# Dionysus_FPGA.net
KiCad netlist of a schematic drawn in Altium Designer
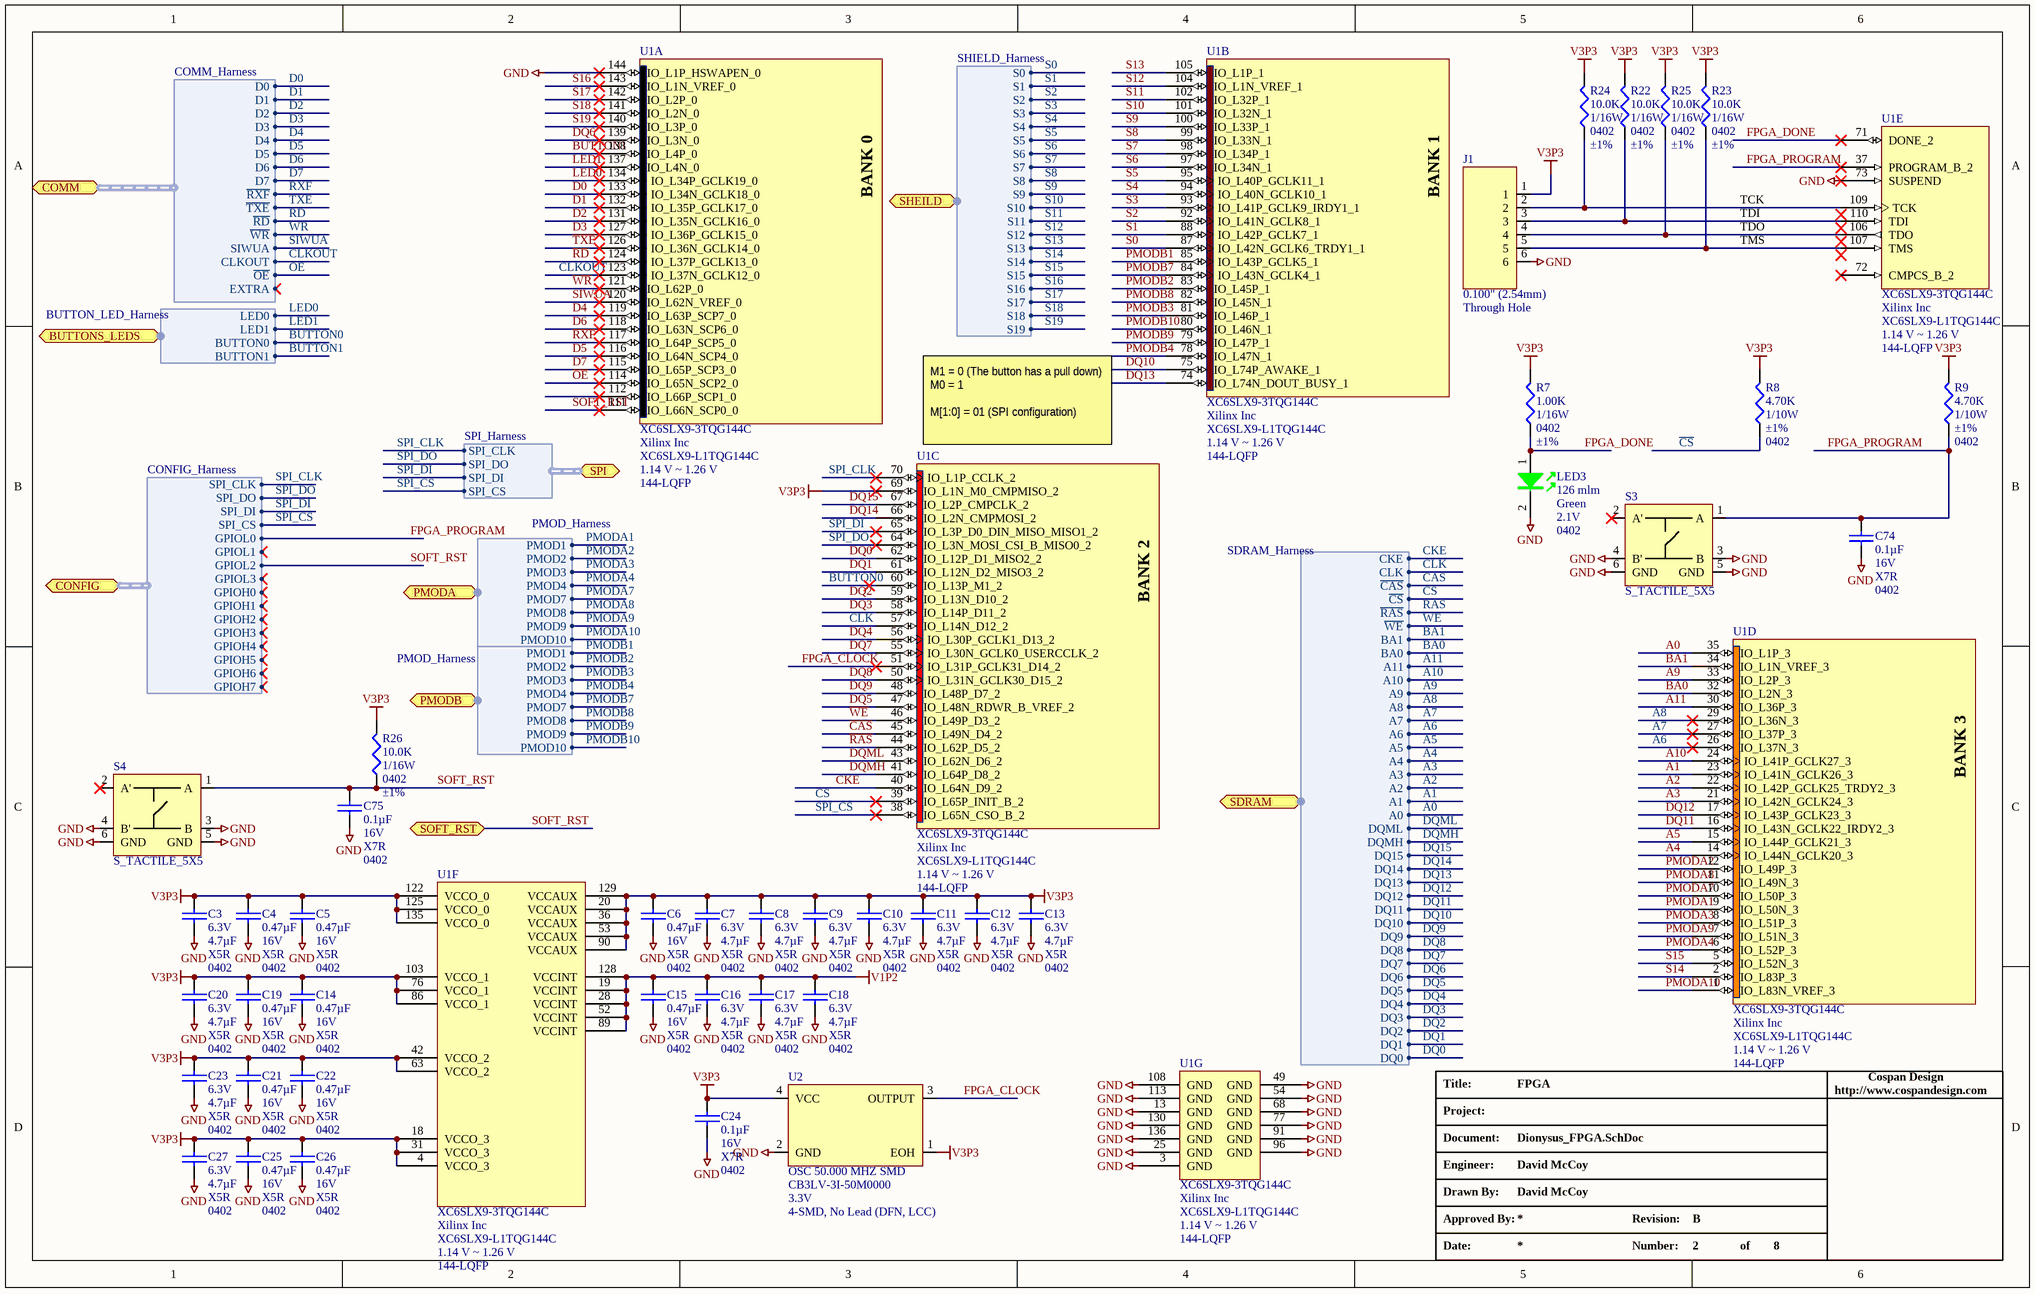
[diagram p0: Dionysus_FPGA.SchDoc]

(export (version "E")
  (design (tool "Eeschema 10.0.6"))
  (components
    (comp (ref "C3")
      (value "4.7uF")
      (footprint "C_ERA-0402")
      (description "CAP CER 4.7UF 6.3V X5R 0402")
      (fields
        (field (name "MANUFACTURER") "Murata Electronics North America")
        (field (name "MANUFACTURER PART NUMBER") "GRM155R60J475ME87D")
        (field (name "VOLTAGE - RATED") "6.3V")
        (field (name "CAPACITANCE") "4.7µF")
        (field (name "TEMPERATURE COEFFICIENT") "X5R")
        (field (name "PACKAGE / CASE") "0402")
      )
      (libsource (lib "Main LibraryX") (part "C_0402_4.7UF"))
    )
    (comp (ref "C4")
      (value "0.47uF")
      (footprint "C_ERA-0402")
      (description "CAP CER .47UF 16V X5R 0402")
      (fields
        (field (name "TOLERANCE") "±10%")
        (field (name "MANUFACTURER") "TDK Corporation")
        (field (name "CAPACITANCE") "0.47µF")
        (field (name "VOLTAGE - RATED") "16V")
        (field (name "TEMPERATURE COEFFICIENT") "X5R")
        (field (name "PACKAGE / CASE") "0402")
      )
      (libsource (lib "Main LibraryX") (part "C_0402_0.47UF"))
    )
    (comp (ref "C5")
      (value "0.47uF")
      (footprint "C_ERA-0402")
      (description "CAP CER .47UF 16V X5R 0402")
      (fields
        (field (name "TOLERANCE") "±10%")
        (field (name "MANUFACTURER") "TDK Corporation")
        (field (name "CAPACITANCE") "0.47µF")
        (field (name "VOLTAGE - RATED") "16V")
        (field (name "TEMPERATURE COEFFICIENT") "X5R")
        (field (name "PACKAGE / CASE") "0402")
      )
      (libsource (lib "Main LibraryX") (part "C_0402_0.47UF"))
    )
    (comp (ref "C6")
      (value "0.47uF")
      (footprint "C_ERA-0402")
      (description "CAP CER .47UF 16V X5R 0402")
      (fields
        (field (name "TOLERANCE") "±10%")
        (field (name "MANUFACTURER") "TDK Corporation")
        (field (name "CAPACITANCE") "0.47µF")
        (field (name "VOLTAGE - RATED") "16V")
        (field (name "TEMPERATURE COEFFICIENT") "X5R")
        (field (name "PACKAGE / CASE") "0402")
      )
      (libsource (lib "Main LibraryX") (part "C_0402_0.47UF"))
    )
    (comp (ref "C7")
      (value "4.7uF")
      (footprint "C_ERA-0402")
      (description "CAP CER 4.7UF 6.3V X5R 0402")
      (fields
        (field (name "MANUFACTURER") "Murata Electronics North America")
        (field (name "MANUFACTURER PART NUMBER") "GRM155R60J475ME87D")
        (field (name "VOLTAGE - RATED") "6.3V")
        (field (name "CAPACITANCE") "4.7µF")
        (field (name "TEMPERATURE COEFFICIENT") "X5R")
        (field (name "PACKAGE / CASE") "0402")
      )
      (libsource (lib "Main LibraryX") (part "C_0402_4.7UF"))
    )
    (comp (ref "C8")
      (value "4.7uF")
      (footprint "C_ERA-0402")
      (description "CAP CER 4.7UF 6.3V X5R 0402")
      (fields
        (field (name "MANUFACTURER") "Murata Electronics North America")
        (field (name "MANUFACTURER PART NUMBER") "GRM155R60J475ME87D")
        (field (name "VOLTAGE - RATED") "6.3V")
        (field (name "CAPACITANCE") "4.7µF")
        (field (name "TEMPERATURE COEFFICIENT") "X5R")
        (field (name "PACKAGE / CASE") "0402")
      )
      (libsource (lib "Main LibraryX") (part "C_0402_4.7UF"))
    )
    (comp (ref "C9")
      (value "4.7uF")
      (footprint "C_ERA-0402")
      (description "CAP CER 4.7UF 6.3V X5R 0402")
      (fields
        (field (name "MANUFACTURER") "Murata Electronics North America")
        (field (name "MANUFACTURER PART NUMBER") "GRM155R60J475ME87D")
        (field (name "VOLTAGE - RATED") "6.3V")
        (field (name "CAPACITANCE") "4.7µF")
        (field (name "TEMPERATURE COEFFICIENT") "X5R")
        (field (name "PACKAGE / CASE") "0402")
      )
      (libsource (lib "Main LibraryX") (part "C_0402_4.7UF"))
    )
    (comp (ref "C10")
      (value "4.7uF")
      (footprint "C_ERA-0402")
      (description "CAP CER 4.7UF 6.3V X5R 0402")
      (fields
        (field (name "MANUFACTURER") "Murata Electronics North America")
        (field (name "MANUFACTURER PART NUMBER") "GRM155R60J475ME87D")
        (field (name "VOLTAGE - RATED") "6.3V")
        (field (name "CAPACITANCE") "4.7µF")
        (field (name "TEMPERATURE COEFFICIENT") "X5R")
        (field (name "PACKAGE / CASE") "0402")
      )
      (libsource (lib "Main LibraryX") (part "C_0402_4.7UF"))
    )
    (comp (ref "C11")
      (value "4.7uF")
      (footprint "C_ERA-0402")
      (description "CAP CER 4.7UF 6.3V X5R 0402")
      (fields
        (field (name "MANUFACTURER") "Murata Electronics North America")
        (field (name "MANUFACTURER PART NUMBER") "GRM155R60J475ME87D")
        (field (name "VOLTAGE - RATED") "6.3V")
        (field (name "CAPACITANCE") "4.7µF")
        (field (name "TEMPERATURE COEFFICIENT") "X5R")
        (field (name "PACKAGE / CASE") "0402")
      )
      (libsource (lib "Main LibraryX") (part "C_0402_4.7UF"))
    )
    (comp (ref "C12")
      (value "4.7uF")
      (footprint "C_ERA-0402")
      (description "CAP CER 4.7UF 6.3V X5R 0402")
      (fields
        (field (name "MANUFACTURER") "Murata Electronics North America")
        (field (name "MANUFACTURER PART NUMBER") "GRM155R60J475ME87D")
        (field (name "VOLTAGE - RATED") "6.3V")
        (field (name "CAPACITANCE") "4.7µF")
        (field (name "TEMPERATURE COEFFICIENT") "X5R")
        (field (name "PACKAGE / CASE") "0402")
      )
      (libsource (lib "Main LibraryX") (part "C_0402_4.7UF"))
    )
    (comp (ref "C13")
      (value "4.7uF")
      (footprint "C_ERA-0402")
      (description "CAP CER 4.7UF 6.3V X5R 0402")
      (fields
        (field (name "MANUFACTURER") "Murata Electronics North America")
        (field (name "MANUFACTURER PART NUMBER") "GRM155R60J475ME87D")
        (field (name "VOLTAGE - RATED") "6.3V")
        (field (name "CAPACITANCE") "4.7µF")
        (field (name "TEMPERATURE COEFFICIENT") "X5R")
        (field (name "PACKAGE / CASE") "0402")
      )
      (libsource (lib "Main LibraryX") (part "C_0402_4.7UF"))
    )
    (comp (ref "C14")
      (value "0.47uF")
      (footprint "C_ERA-0402")
      (description "CAP CER .47UF 16V X5R 0402")
      (fields
        (field (name "TOLERANCE") "±10%")
        (field (name "MANUFACTURER") "TDK Corporation")
        (field (name "CAPACITANCE") "0.47µF")
        (field (name "VOLTAGE - RATED") "16V")
        (field (name "TEMPERATURE COEFFICIENT") "X5R")
        (field (name "PACKAGE / CASE") "0402")
      )
      (libsource (lib "Main LibraryX") (part "C_0402_0.47UF"))
    )
    (comp (ref "C15")
      (value "0.47uF")
      (footprint "C_ERA-0402")
      (description "CAP CER .47UF 16V X5R 0402")
      (fields
        (field (name "TOLERANCE") "±10%")
        (field (name "MANUFACTURER") "TDK Corporation")
        (field (name "CAPACITANCE") "0.47µF")
        (field (name "VOLTAGE - RATED") "16V")
        (field (name "TEMPERATURE COEFFICIENT") "X5R")
        (field (name "PACKAGE / CASE") "0402")
      )
      (libsource (lib "Main LibraryX") (part "C_0402_0.47UF"))
    )
    (comp (ref "C16")
      (value "4.7uF")
      (footprint "C_ERA-0402")
      (description "CAP CER 4.7UF 6.3V X5R 0402")
      (fields
        (field (name "MANUFACTURER") "Murata Electronics North America")
        (field (name "MANUFACTURER PART NUMBER") "GRM155R60J475ME87D")
        (field (name "VOLTAGE - RATED") "6.3V")
        (field (name "CAPACITANCE") "4.7µF")
        (field (name "TEMPERATURE COEFFICIENT") "X5R")
        (field (name "PACKAGE / CASE") "0402")
      )
      (libsource (lib "Main LibraryX") (part "C_0402_4.7UF"))
    )
    (comp (ref "C17")
      (value "4.7uF")
      (footprint "C_ERA-0402")
      (description "CAP CER 4.7UF 6.3V X5R 0402")
      (fields
        (field (name "MANUFACTURER") "Murata Electronics North America")
        (field (name "MANUFACTURER PART NUMBER") "GRM155R60J475ME87D")
        (field (name "VOLTAGE - RATED") "6.3V")
        (field (name "CAPACITANCE") "4.7µF")
        (field (name "TEMPERATURE COEFFICIENT") "X5R")
        (field (name "PACKAGE / CASE") "0402")
      )
      (libsource (lib "Main LibraryX") (part "C_0402_4.7UF"))
    )
    (comp (ref "C18")
      (value "4.7uF")
      (footprint "C_ERA-0402")
      (description "CAP CER 4.7UF 6.3V X5R 0402")
      (fields
        (field (name "MANUFACTURER") "Murata Electronics North America")
        (field (name "MANUFACTURER PART NUMBER") "GRM155R60J475ME87D")
        (field (name "VOLTAGE - RATED") "6.3V")
        (field (name "CAPACITANCE") "4.7µF")
        (field (name "TEMPERATURE COEFFICIENT") "X5R")
        (field (name "PACKAGE / CASE") "0402")
      )
      (libsource (lib "Main LibraryX") (part "C_0402_4.7UF"))
    )
    (comp (ref "C19")
      (value "0.47uF")
      (footprint "C_ERA-0402")
      (description "CAP CER .47UF 16V X5R 0402")
      (fields
        (field (name "TOLERANCE") "±10%")
        (field (name "MANUFACTURER") "TDK Corporation")
        (field (name "CAPACITANCE") "0.47µF")
        (field (name "VOLTAGE - RATED") "16V")
        (field (name "TEMPERATURE COEFFICIENT") "X5R")
        (field (name "PACKAGE / CASE") "0402")
      )
      (libsource (lib "Main LibraryX") (part "C_0402_0.47UF"))
    )
    (comp (ref "C20")
      (value "4.7uF")
      (footprint "C_ERA-0402")
      (description "CAP CER 4.7UF 6.3V X5R 0402")
      (fields
        (field (name "MANUFACTURER") "Murata Electronics North America")
        (field (name "MANUFACTURER PART NUMBER") "GRM155R60J475ME87D")
        (field (name "VOLTAGE - RATED") "6.3V")
        (field (name "CAPACITANCE") "4.7µF")
        (field (name "TEMPERATURE COEFFICIENT") "X5R")
        (field (name "PACKAGE / CASE") "0402")
      )
      (libsource (lib "Main LibraryX") (part "C_0402_4.7UF"))
    )
    (comp (ref "C21")
      (value "0.47uF")
      (footprint "C_ERA-0402")
      (description "CAP CER .47UF 16V X5R 0402")
      (fields
        (field (name "TOLERANCE") "±10%")
        (field (name "MANUFACTURER") "TDK Corporation")
        (field (name "CAPACITANCE") "0.47µF")
        (field (name "VOLTAGE - RATED") "16V")
        (field (name "TEMPERATURE COEFFICIENT") "X5R")
        (field (name "PACKAGE / CASE") "0402")
      )
      (libsource (lib "Main LibraryX") (part "C_0402_0.47UF"))
    )
    (comp (ref "C22")
      (value "0.47uF")
      (footprint "C_ERA-0402")
      (description "CAP CER .47UF 16V X5R 0402")
      (fields
        (field (name "TOLERANCE") "±10%")
        (field (name "MANUFACTURER") "TDK Corporation")
        (field (name "CAPACITANCE") "0.47µF")
        (field (name "VOLTAGE - RATED") "16V")
        (field (name "TEMPERATURE COEFFICIENT") "X5R")
        (field (name "PACKAGE / CASE") "0402")
      )
      (libsource (lib "Main LibraryX") (part "C_0402_0.47UF"))
    )
    (comp (ref "C23")
      (value "4.7uF")
      (footprint "C_ERA-0402")
      (description "CAP CER 4.7UF 6.3V X5R 0402")
      (fields
        (field (name "MANUFACTURER") "Murata Electronics North America")
        (field (name "MANUFACTURER PART NUMBER") "GRM155R60J475ME87D")
        (field (name "VOLTAGE - RATED") "6.3V")
        (field (name "CAPACITANCE") "4.7µF")
        (field (name "TEMPERATURE COEFFICIENT") "X5R")
        (field (name "PACKAGE / CASE") "0402")
      )
      (libsource (lib "Main LibraryX") (part "C_0402_4.7UF"))
    )
    (comp (ref "C24")
      (value "0.1uF")
      (footprint "C_ERA-0402")
      (description "CAP CER .10UF 16V X7R 0402")
      (fields
        (field (name "MANUFACTURER") "TDK Corporation")
        (field (name "MANUFACTURER PART NUMBER") "C1005X7R1C104K")
        (field (name "CAPACITANCE") "0.1µF")
        (field (name "VOLTAGE - RATED") "16V")
        (field (name "TEMPERATURE COEFFICIENT") "X7R")
        (field (name "PACKAGE / CASE") "0402")
      )
      (libsource (lib "Main LibraryX") (part "C_0402_0.1UF_16V"))
    )
    (comp (ref "C25")
      (value "0.47uF")
      (footprint "C_ERA-0402")
      (description "CAP CER .47UF 16V X5R 0402")
      (fields
        (field (name "TOLERANCE") "±10%")
        (field (name "MANUFACTURER") "TDK Corporation")
        (field (name "CAPACITANCE") "0.47µF")
        (field (name "VOLTAGE - RATED") "16V")
        (field (name "TEMPERATURE COEFFICIENT") "X5R")
        (field (name "PACKAGE / CASE") "0402")
      )
      (libsource (lib "Main LibraryX") (part "C_0402_0.47UF"))
    )
    (comp (ref "C26")
      (value "0.47uF")
      (footprint "C_ERA-0402")
      (description "CAP CER .47UF 16V X5R 0402")
      (fields
        (field (name "TOLERANCE") "±10%")
        (field (name "MANUFACTURER") "TDK Corporation")
        (field (name "CAPACITANCE") "0.47µF")
        (field (name "VOLTAGE - RATED") "16V")
        (field (name "TEMPERATURE COEFFICIENT") "X5R")
        (field (name "PACKAGE / CASE") "0402")
      )
      (libsource (lib "Main LibraryX") (part "C_0402_0.47UF"))
    )
    (comp (ref "C27")
      (value "4.7uF")
      (footprint "C_ERA-0402")
      (description "CAP CER 4.7UF 6.3V X5R 0402")
      (fields
        (field (name "MANUFACTURER") "Murata Electronics North America")
        (field (name "MANUFACTURER PART NUMBER") "GRM155R60J475ME87D")
        (field (name "VOLTAGE - RATED") "6.3V")
        (field (name "CAPACITANCE") "4.7µF")
        (field (name "TEMPERATURE COEFFICIENT") "X5R")
        (field (name "PACKAGE / CASE") "0402")
      )
      (libsource (lib "Main LibraryX") (part "C_0402_4.7UF"))
    )
    (comp (ref "C74")
      (value "0.1uF")
      (footprint "C_ERA-0402")
      (description "CAP CER .10UF 16V X7R 0402")
      (fields
        (field (name "MANUFACTURER") "TDK Corporation")
        (field (name "MANUFACTURER PART NUMBER") "C1005X7R1C104K")
        (field (name "CAPACITANCE") "0.1µF")
        (field (name "VOLTAGE - RATED") "16V")
        (field (name "TEMPERATURE COEFFICIENT") "X7R")
        (field (name "PACKAGE / CASE") "0402")
      )
      (libsource (lib "Main LibraryX") (part "C_0402_0.1UF_16V"))
    )
    (comp (ref "C75")
      (value "0.1uF")
      (footprint "C_ERA-0402")
      (description "CAP CER .10UF 16V X7R 0402")
      (fields
        (field (name "MANUFACTURER") "TDK Corporation")
        (field (name "MANUFACTURER PART NUMBER") "C1005X7R1C104K")
        (field (name "CAPACITANCE") "0.1µF")
        (field (name "VOLTAGE - RATED") "16V")
        (field (name "TEMPERATURE COEFFICIENT") "X7R")
        (field (name "PACKAGE / CASE") "0402")
      )
      (libsource (lib "Main LibraryX") (part "C_0402_0.1UF_16V"))
    )
    (comp (ref "J1")
      (value "J_HDR1X6_THRHOLE_VERT")
      (footprint "HDR_1X6")
      (description "CONN HEADER .100\" 12POS TIN PCB")
      (fields
        (field (name "MANUFACTURER") "Samtec")
        (field (name "MANUFACTURER PART NUMBER") "TSW-106-07-T-S")
        (field (name "PITCH") "0.100\" (2.54mm)")
        (field (name "MOUNTING TYPE") "Through Hole")
      )
      (libsource (lib "Main LibraryX") (part "J_HDR1X6_THRHOLE_VERT"))
    )
    (comp (ref "LED3")
      (value "LED_GRN_0402")
      (footprint "DIOM1005X07L_GREEN")
      (description "LED 1X0.5MM 570NM GN WTR CLR SMD")
      (fields
        (field (name "MANUFACTURER") "Kingbright Corp")
        (field (name "MANUFACTURER PART NUMBER") "APHHS1005CGCK")
        (field (name "LUMINOUS FLUX @ CURRENT - TEST") "126 mlm")
        (field (name "COLOR") "Green")
        (field (name "VOLTAGE - FORWARD (VF) TYP") "2.1V")
        (field (name "PACKAGE / CASE") "0402")
      )
      (libsource (lib "Main Library") (part "LED_GRN_0402"))
    )
    (comp (ref "R7")
      (value "1.0k Ohms")
      (footprint "ERA-0402")
      (description "RES 1.00K OHM 1/16W 1% 0402 SMD")
      (fields
        (field (name "MANUFACTURER") "Yageo")
        (field (name "MANUFACTURER PART NUMBER") "RC0402FR-071KL")
        (field (name "RESISTANCE IN OHMS") "1.00K")
        (field (name "POWER (WATTS)") "1/16W")
        (field (name "CASE") "0402")
        (field (name "TOLERANCE") "±1%")
      )
      (libsource (lib "Main Library") (part "R_0402_1.0K"))
    )
    (comp (ref "R8")
      (value "4.7k Ohms")
      (footprint "ERA-0402")
      (description "RES 4.70K OHM 1/10W 1% 0402 SMD")
      (fields
        (field (name "MANUFACTURER") "Yageo")
        (field (name "MANUFACTURER PART NUMBER") "RC0402FR-074K7L")
        (field (name "RESISTANCE IN OHMS") "4.70K")
        (field (name "POWER (WATTS)") "1/10W")
        (field (name "TOLERANCE") "±1%")
        (field (name "CASE") "0402")
      )
      (libsource (lib "Main LibraryX") (part "R_0402_4.70K"))
    )
    (comp (ref "R9")
      (value "4.7k Ohms")
      (footprint "ERA-0402")
      (description "RES 4.70K OHM 1/10W 1% 0402 SMD")
      (fields
        (field (name "MANUFACTURER") "Yageo")
        (field (name "MANUFACTURER PART NUMBER") "RC0402FR-074K7L")
        (field (name "RESISTANCE IN OHMS") "4.70K")
        (field (name "POWER (WATTS)") "1/10W")
        (field (name "TOLERANCE") "±1%")
        (field (name "CASE") "0402")
      )
      (libsource (lib "Main LibraryX") (part "R_0402_4.70K"))
    )
    (comp (ref "R22")
      (value "R_0402_10.0K")
      (footprint "ERA-0402")
      (description "RES 10.0K OHM 1/16W 1% 0402 SMD")
      (fields
        (field (name "MANUFACTURER") "Stackpole Electronics Inc")
        (field (name "MANUFACTURER PART NUMBER") "RMCF0402FT10K0")
        (field (name "RESISTANCE IN OHMS") "10.0K")
        (field (name "POWER (WATTS)") "1/16W")
        (field (name "CASE") "0402")
        (field (name "TOLERANCE") "±1%")
      )
      (libsource (lib "Main LibraryX") (part "R_0402_10.0K"))
    )
    (comp (ref "R23")
      (value "R_0402_10.0K")
      (footprint "ERA-0402")
      (description "RES 10.0K OHM 1/16W 1% 0402 SMD")
      (fields
        (field (name "MANUFACTURER") "Stackpole Electronics Inc")
        (field (name "MANUFACTURER PART NUMBER") "RMCF0402FT10K0")
        (field (name "RESISTANCE IN OHMS") "10.0K")
        (field (name "POWER (WATTS)") "1/16W")
        (field (name "CASE") "0402")
        (field (name "TOLERANCE") "±1%")
      )
      (libsource (lib "Main LibraryX") (part "R_0402_10.0K"))
    )
    (comp (ref "R24")
      (value "R_0402_10.0K")
      (footprint "ERA-0402")
      (description "RES 10.0K OHM 1/16W 1% 0402 SMD")
      (fields
        (field (name "MANUFACTURER") "Stackpole Electronics Inc")
        (field (name "MANUFACTURER PART NUMBER") "RMCF0402FT10K0")
        (field (name "RESISTANCE IN OHMS") "10.0K")
        (field (name "POWER (WATTS)") "1/16W")
        (field (name "CASE") "0402")
        (field (name "TOLERANCE") "±1%")
      )
      (libsource (lib "Main LibraryX") (part "R_0402_10.0K"))
    )
    (comp (ref "R25")
      (value "R_0402_10.0K")
      (footprint "ERA-0402")
      (description "RES 10.0K OHM 1/16W 1% 0402 SMD")
      (fields
        (field (name "MANUFACTURER") "Stackpole Electronics Inc")
        (field (name "MANUFACTURER PART NUMBER") "RMCF0402FT10K0")
        (field (name "RESISTANCE IN OHMS") "10.0K")
        (field (name "POWER (WATTS)") "1/16W")
        (field (name "CASE") "0402")
        (field (name "TOLERANCE") "±1%")
      )
      (libsource (lib "Main LibraryX") (part "R_0402_10.0K"))
    )
    (comp (ref "R26")
      (value "R_0402_10.0K")
      (footprint "ERA-0402")
      (description "RES 10.0K OHM 1/16W 1% 0402 SMD")
      (fields
        (field (name "MANUFACTURER") "Stackpole Electronics Inc")
        (field (name "MANUFACTURER PART NUMBER") "RMCF0402FT10K0")
        (field (name "RESISTANCE IN OHMS") "10.0K")
        (field (name "POWER (WATTS)") "1/16W")
        (field (name "CASE") "0402")
        (field (name "TOLERANCE") "±1%")
      )
      (libsource (lib "Main LibraryX") (part "R_0402_10.0K"))
    )
    (comp (ref "S3")
      (value "S_TACTILE_5X5")
      (footprint "TACTILE_BUTTON_5X5")
      (description "SWITCH LT 1.5MM HT 160GF SMD")
      (fields
        (field (name "MANUFACTURER") "Panasonic - ECG")
        (field (name "MANUFACTURER PART NUMBER") "EVQ-PLHA15")
      )
      (libsource (lib "Main Library") (part "S_TACTILE_5X5"))
    )
    (comp (ref "S4")
      (value "S_TACTILE_5X5")
      (footprint "TACTILE_BUTTON_5X5")
      (description "SWITCH LT 1.5MM HT 160GF SMD")
      (fields
        (field (name "MANUFACTURER") "Panasonic - ECG")
        (field (name "MANUFACTURER PART NUMBER") "EVQ-PLHA15")
      )
      (libsource (lib "Main Library") (part "S_TACTILE_5X5"))
    )
    (comp (ref "U1")
      (value "XC6SLX9-3TQG144C")
      (footprint "TQG144_N")
      (description "IC FPAG SPARTAN 6 9K 144TQFP")
      (fields
        (field (name "MANUFACTURER") "Xilinx Inc")
        (field (name "MANUFACTURER PART NUMBER") "XC6SLX9-L1TQG144C")
        (field (name "VOLTAGE - SUPPLY") "1.14 V ~ 1.26 V")
        (field (name "PACKAGE / CASE") "144-LQFP")
      )
      (libsource (lib "") (part "U_XC6SLX9-3TQG144C_1"))
    )
    (comp (ref "U2")
      (value "OSC 50.000 MHZ SMD")
      (footprint "SMD_OSC_12MHZ")
      (description "OSC 50.0000 MHZ 3.3V SMD")
      (fields
        (field (name "MANUFACTURER") "CTS-Frequency Controls")
        (field (name "MANUFACTURER PART NUMBER") "CB3LV-3I-50M0000")
        (field (name "SUPPLY VOLTAGE") "3.3V")
        (field (name "PACKAGE / CASE") "4-SMD, No Lead (DFN, LCC)")
      )
      (libsource (lib "Main Library") (part "U_OSC_50MHZ_SMD"))
    )
  )
  (nets
    (net (code "8") (name "/A0") (class "Default")
      (node (ref "U1") (pin "35") (pinfunction "IO_L1P_3_35") (pintype "bidirectional"))
    )
    (net (code "9") (name "/A1") (class "Default")
      (node (ref "U1") (pin "23") (pinfunction "IO_L41N_GCLK26_3_23") (pintype "bidirectional"))
    )
    (net (code "10") (name "/A2") (class "Default")
      (node (ref "U1") (pin "22") (pinfunction "IO_L42P_GCLK25_TRDY2_3_22") (pintype "bidirectional"))
    )
    (net (code "11") (name "/A3") (class "Default")
      (node (ref "U1") (pin "21") (pinfunction "IO_L42N_GCLK24_3_21") (pintype "bidirectional"))
    )
    (net (code "12") (name "/A4") (class "Default")
      (node (ref "U1") (pin "14") (pinfunction "IO_L44N_GCLK20_3_14") (pintype "bidirectional"))
    )
    (net (code "13") (name "/A5") (class "Default")
      (node (ref "U1") (pin "15") (pinfunction "IO_L44P_GCLK21_3_15") (pintype "bidirectional"))
    )
    (net (code "14") (name "/A6") (class "Default")
      (node (ref "U1") (pin "26") (pinfunction "IO_L37N_3_26") (pintype "bidirectional"))
    )
    (net (code "15") (name "/A7") (class "Default")
      (node (ref "U1") (pin "27") (pinfunction "IO_L37P_3_27") (pintype "bidirectional"))
    )
    (net (code "16") (name "/A8") (class "Default")
      (node (ref "U1") (pin "29") (pinfunction "IO_L36N_3_29") (pintype "bidirectional"))
    )
    (net (code "17") (name "/A9") (class "Default")
      (node (ref "U1") (pin "33") (pinfunction "IO_L2P_3_33") (pintype "bidirectional"))
    )
    (net (code "18") (name "/A10") (class "Default")
      (node (ref "U1") (pin "24") (pinfunction "IO_L41P_GCLK27_3_24") (pintype "bidirectional"))
    )
    (net (code "19") (name "/A11") (class "Default")
      (node (ref "U1") (pin "30") (pinfunction "IO_L36P_3_30") (pintype "bidirectional"))
    )
    (net (code "20") (name "/BA0") (class "Default")
      (node (ref "U1") (pin "32") (pinfunction "IO_L2N_3_32") (pintype "bidirectional"))
    )
    (net (code "21") (name "/BA1") (class "Default")
      (node (ref "U1") (pin "34") (pinfunction "IO_L1N_VREF_3_34") (pintype "bidirectional"))
    )
    (net (code "22") (name "/BUTTON0") (class "Default")
      (node (ref "U1") (pin "60") (pinfunction "IO_L13P_M1_2_60") (pintype "bidirectional"))
    )
    (net (code "23") (name "/BUTTON1") (class "Default")
      (node (ref "U1") (pin "138") (pinfunction "IO_L4P_0_138") (pintype "bidirectional"))
    )
    (net (code "24") (name "/CKE") (class "Default")
      (node (ref "U1") (pin "40") (pinfunction "IO_L64N_D9_2_40") (pintype "bidirectional"))
    )
    (net (code "25") (name "/CLK") (class "Default")
      (node (ref "U1") (pin "57") (pinfunction "IO_L14N_D12_2_57") (pintype "bidirectional"))
    )
    (net (code "26") (name "/CLKOUT") (class "Default")
      (node (ref "U1") (pin "123") (pinfunction "IO_L37N_GCLK12_0_123") (pintype "bidirectional+no_connect"))
    )
    (net (code "27") (name "/D0") (class "Default")
      (node (ref "U1") (pin "133") (pinfunction "IO_L34N_GCLK18_0_133") (pintype "bidirectional"))
    )
    (net (code "28") (name "/D1") (class "Default")
      (node (ref "U1") (pin "132") (pinfunction "IO_L35P_GCLK17_0_132") (pintype "bidirectional"))
    )
    (net (code "29") (name "/D2") (class "Default")
      (node (ref "U1") (pin "131") (pinfunction "IO_L35N_GCLK16_0_131") (pintype "bidirectional"))
    )
    (net (code "30") (name "/D3") (class "Default")
      (node (ref "U1") (pin "127") (pinfunction "IO_L36P_GCLK15_0_127") (pintype "bidirectional+no_connect"))
    )
    (net (code "31") (name "/D4") (class "Default")
      (node (ref "U1") (pin "119") (pinfunction "IO_L63P_SCP7_0_119") (pintype "bidirectional+no_connect"))
    )
    (net (code "32") (name "/D5") (class "Default")
      (node (ref "U1") (pin "116") (pinfunction "IO_L64N_SCP4_0_116") (pintype "bidirectional"))
    )
    (net (code "33") (name "/D6") (class "Default")
      (node (ref "U1") (pin "118") (pinfunction "IO_L63N_SCP6_0_118") (pintype "bidirectional+no_connect"))
    )
    (net (code "34") (name "/D7") (class "Default")
      (node (ref "U1") (pin "115") (pinfunction "IO_L65P_SCP3_0_115") (pintype "bidirectional"))
    )
    (net (code "35") (name "/DQ0") (class "Default")
      (node (ref "U1") (pin "62") (pinfunction "IO_L12P_D1_MISO2_2_62") (pintype "bidirectional"))
    )
    (net (code "36") (name "/DQ1") (class "Default")
      (node (ref "U1") (pin "61") (pinfunction "IO_L12N_D2_MISO3_2_61") (pintype "bidirectional"))
    )
    (net (code "37") (name "/DQ2") (class "Default")
      (node (ref "U1") (pin "59") (pinfunction "IO_L13N_D10_2_59") (pintype "bidirectional"))
    )
    (net (code "38") (name "/DQ3") (class "Default")
      (node (ref "U1") (pin "58") (pinfunction "IO_L14P_D11_2_58") (pintype "bidirectional"))
    )
    (net (code "39") (name "/DQ4") (class "Default")
      (node (ref "U1") (pin "56") (pinfunction "IO_L30P_GCLK1_D13_2_56") (pintype "bidirectional"))
    )
    (net (code "40") (name "/DQ5") (class "Default")
      (node (ref "U1") (pin "47") (pinfunction "IO_L48N_RDWR_B_VREF_2_47") (pintype "bidirectional"))
    )
    (net (code "41") (name "/DQ6") (class "Default")
      (node (ref "U1") (pin "139") (pinfunction "IO_L3N_0_139") (pintype "bidirectional+no_connect"))
    )
    (net (code "42") (name "/DQ7") (class "Default")
      (node (ref "U1") (pin "55") (pinfunction "IO_L30N_GCLK0_USERCCLK_2_55") (pintype "bidirectional"))
    )
    (net (code "43") (name "/DQ8") (class "Default")
      (node (ref "U1") (pin "50") (pinfunction "IO_L31N_GCLK30_D15_2_50") (pintype "bidirectional"))
    )
    (net (code "44") (name "/DQ9") (class "Default")
      (node (ref "U1") (pin "48") (pinfunction "IO_L48P_D7_2_48") (pintype "bidirectional"))
    )
    (net (code "45") (name "/DQ10") (class "Default")
      (node (ref "U1") (pin "75") (pinfunction "IO_L74P_AWAKE_1_75") (pintype "bidirectional"))
    )
    (net (code "46") (name "/DQ11") (class "Default")
      (node (ref "U1") (pin "16") (pinfunction "IO_L43N_GCLK22_IRDY2_3_16") (pintype "bidirectional"))
    )
    (net (code "47") (name "/DQ12") (class "Default")
      (node (ref "U1") (pin "17") (pinfunction "IO_L43P_GCLK23_3_17") (pintype "bidirectional"))
    )
    (net (code "48") (name "/DQ13") (class "Default")
      (node (ref "U1") (pin "74") (pinfunction "IO_L74N_DOUT_BUSY_1_74") (pintype "bidirectional"))
    )
    (net (code "49") (name "/DQ14") (class "Default")
      (node (ref "U1") (pin "66") (pinfunction "IO_L2N_CMPMOSI_2_66") (pintype "bidirectional"))
    )
    (net (code "50") (name "/DQ15") (class "Default")
      (node (ref "U1") (pin "67") (pinfunction "IO_L2P_CMPCLK_2_67") (pintype "bidirectional"))
    )
    (net (code "51") (name "/DQMH") (class "Default")
      (node (ref "U1") (pin "41") (pinfunction "IO_L64P_D8_2_41") (pintype "bidirectional"))
    )
    (net (code "52") (name "/DQML") (class "Default")
      (node (ref "U1") (pin "43") (pinfunction "IO_L62N_D6_2_43") (pintype "bidirectional"))
    )
    (net (code "53") (name "/FPGA_CLOCK") (class "Default")
      (node (ref "U1") (pin "51") (pinfunction "IO_L31P_GCLK31_D14_2_51") (pintype "bidirectional"))
      (node (ref "U2") (pin "3") (pinfunction "OUTPUT_3") (pintype "passive"))
    )
    (net (code "54") (name "/FPGA_DONE") (class "Default")
      (node (ref "LED3") (pin "1") (pinfunction "1_1") (pintype "passive"))
      (node (ref "R7") (pin "2") (pinfunction "2_2") (pintype "passive"))
      (node (ref "U1") (pin "71") (pinfunction "DONE_2_71") (pintype "bidirectional"))
    )
    (net (code "55") (name "/FPGA_PROGRAM") (class "Default")
      (node (ref "C74") (pin "2") (pinfunction "2_2") (pintype "passive"))
      (node (ref "R9") (pin "2") (pinfunction "2_2") (pintype "passive"))
      (node (ref "S3") (pin "1") (pinfunction "A_1") (pintype "passive"))
      (node (ref "U1") (pin "37") (pinfunction "PROGRAM_B_2_37") (pintype "input"))
    )
    (net (code "56") (name "/LED0") (class "Default")
      (node (ref "U1") (pin "134") (pinfunction "IO_L34P_GCLK19_0_134") (pintype "bidirectional"))
    )
    (net (code "57") (name "/LED1") (class "Default")
      (node (ref "U1") (pin "137") (pinfunction "IO_L4N_0_137") (pintype "bidirectional"))
    )
    (net (code "58") (name "/PMODA1") (class "Default")
      (node (ref "U1") (pin "9") (pinfunction "IO_L50N_3_9") (pintype "bidirectional"))
    )
    (net (code "59") (name "/PMODA2") (class "Default")
      (node (ref "U1") (pin "12") (pinfunction "IO_L49P_3_12") (pintype "bidirectional"))
    )
    (net (code "60") (name "/PMODA3") (class "Default")
      (node (ref "U1") (pin "8") (pinfunction "IO_L51P_3_8") (pintype "bidirectional"))
    )
    (net (code "61") (name "/PMODA4") (class "Default")
      (node (ref "U1") (pin "6") (pinfunction "IO_L52P_3_6") (pintype "bidirectional"))
    )
    (net (code "62") (name "/PMODA7") (class "Default")
      (node (ref "U1") (pin "10") (pinfunction "IO_L50P_3_10") (pintype "bidirectional"))
    )
    (net (code "63") (name "/PMODA8") (class "Default")
      (node (ref "U1") (pin "11") (pinfunction "IO_L49N_3_11") (pintype "bidirectional"))
    )
    (net (code "64") (name "/PMODA9") (class "Default")
      (node (ref "U1") (pin "7") (pinfunction "IO_L51N_3_7") (pintype "bidirectional"))
    )
    (net (code "65") (name "/PMODA10") (class "Default")
      (node (ref "U1") (pin "1") (pinfunction "IO_L83N_VREF_3_1") (pintype "bidirectional"))
    )
    (net (code "66") (name "/PMODB1") (class "Default")
      (node (ref "U1") (pin "85") (pinfunction "IO_L43P_GCLK5_1_85") (pintype "bidirectional"))
    )
    (net (code "67") (name "/PMODB2") (class "Default")
      (node (ref "U1") (pin "83") (pinfunction "IO_L45P_1_83") (pintype "bidirectional"))
    )
    (net (code "68") (name "/PMODB3") (class "Default")
      (node (ref "U1") (pin "81") (pinfunction "IO_L46P_1_81") (pintype "bidirectional"))
    )
    (net (code "69") (name "/PMODB4") (class "Default")
      (node (ref "U1") (pin "78") (pinfunction "IO_L47N_1_78") (pintype "bidirectional"))
    )
    (net (code "70") (name "/PMODB7") (class "Default")
      (node (ref "U1") (pin "84") (pinfunction "IO_L43N_GCLK4_1_84") (pintype "bidirectional"))
    )
    (net (code "71") (name "/PMODB8") (class "Default")
      (node (ref "U1") (pin "82") (pinfunction "IO_L45N_1_82") (pintype "bidirectional"))
    )
    (net (code "72") (name "/PMODB9") (class "Default")
      (node (ref "U1") (pin "79") (pinfunction "IO_L47P_1_79") (pintype "bidirectional"))
    )
    (net (code "73") (name "/PMODB10") (class "Default")
      (node (ref "U1") (pin "80") (pinfunction "IO_L46N_1_80") (pintype "bidirectional"))
    )
    (net (code "74") (name "/S0") (class "Default")
      (node (ref "U1") (pin "87") (pinfunction "IO_L42N_GCLK6_TRDY1_1_87") (pintype "bidirectional"))
    )
    (net (code "75") (name "/S1") (class "Default")
      (node (ref "U1") (pin "88") (pinfunction "IO_L42P_GCLK7_1_88") (pintype "bidirectional"))
    )
    (net (code "76") (name "/S2") (class "Default")
      (node (ref "U1") (pin "92") (pinfunction "IO_L41N_GCLK8_1_92") (pintype "bidirectional"))
    )
    (net (code "77") (name "/S3") (class "Default")
      (node (ref "U1") (pin "93") (pinfunction "IO_L41P_GCLK9_IRDY1_1_93") (pintype "bidirectional"))
    )
    (net (code "78") (name "/S4") (class "Default")
      (node (ref "U1") (pin "94") (pinfunction "IO_L40N_GCLK10_1_94") (pintype "bidirectional"))
    )
    (net (code "79") (name "/S5") (class "Default")
      (node (ref "U1") (pin "95") (pinfunction "IO_L40P_GCLK11_1_95") (pintype "bidirectional"))
    )
    (net (code "80") (name "/S6") (class "Default")
      (node (ref "U1") (pin "97") (pinfunction "IO_L34N_1_97") (pintype "bidirectional"))
    )
    (net (code "81") (name "/S7") (class "Default")
      (node (ref "U1") (pin "98") (pinfunction "IO_L34P_1_98") (pintype "bidirectional"))
    )
    (net (code "82") (name "/S8") (class "Default")
      (node (ref "U1") (pin "99") (pinfunction "IO_L33N_1_99") (pintype "bidirectional"))
    )
    (net (code "83") (name "/S9") (class "Default")
      (node (ref "U1") (pin "100") (pinfunction "IO_L33P_1_100") (pintype "bidirectional"))
    )
    (net (code "84") (name "/S10") (class "Default")
      (node (ref "U1") (pin "101") (pinfunction "IO_L32N_1_101") (pintype "bidirectional"))
    )
    (net (code "85") (name "/S11") (class "Default")
      (node (ref "U1") (pin "102") (pinfunction "IO_L32P_1_102") (pintype "bidirectional"))
    )
    (net (code "86") (name "/S12") (class "Default")
      (node (ref "U1") (pin "104") (pinfunction "IO_L1N_VREF_1_104") (pintype "bidirectional"))
    )
    (net (code "87") (name "/S13") (class "Default")
      (node (ref "U1") (pin "105") (pinfunction "IO_L1P_1_105") (pintype "bidirectional"))
    )
    (net (code "88") (name "/S14") (class "Default")
      (node (ref "U1") (pin "2") (pinfunction "IO_L83P_3_2") (pintype "bidirectional"))
    )
    (net (code "89") (name "/S15") (class "Default")
      (node (ref "U1") (pin "5") (pinfunction "IO_L52N_3_5") (pintype "bidirectional"))
    )
    (net (code "90") (name "/S16") (class "Default")
      (node (ref "U1") (pin "143") (pinfunction "IO_L1N_VREF_0_143") (pintype "bidirectional+no_connect"))
    )
    (net (code "91") (name "/S17") (class "Default")
      (node (ref "U1") (pin "142") (pinfunction "IO_L2P_0_142") (pintype "bidirectional+no_connect"))
    )
    (net (code "92") (name "/S18") (class "Default")
      (node (ref "U1") (pin "141") (pinfunction "IO_L2N_0_141") (pintype "bidirectional+no_connect"))
    )
    (net (code "93") (name "/S19") (class "Default")
      (node (ref "U1") (pin "140") (pinfunction "IO_L3P_0_140") (pintype "bidirectional+no_connect"))
    )
    (net (code "94") (name "/SIWUA") (class "Default")
      (node (ref "U1") (pin "120") (pinfunction "IO_L62N_VREF_0_120") (pintype "bidirectional+no_connect"))
    )
    (net (code "95") (name "/SOFT_RST") (class "Default")
      (node (ref "C75") (pin "2") (pinfunction "2_2") (pintype "passive"))
      (node (ref "R26") (pin "2") (pinfunction "2_2") (pintype "passive"))
      (node (ref "S4") (pin "1") (pinfunction "A_1") (pintype "passive"))
      (node (ref "U1") (pin "111") (pinfunction "IO_L66N_SCP0_0_111") (pintype "bidirectional"))
    )
    (net (code "96") (name "/SPI_CLK") (class "Default")
      (node (ref "U1") (pin "70") (pinfunction "IO_L1P_CCLK_2_70") (pintype "bidirectional"))
    )
    (net (code "97") (name "/SPI_CS") (class "Default")
      (node (ref "U1") (pin "38") (pinfunction "IO_L65N_CSO_B_2_38") (pintype "bidirectional"))
    )
    (net (code "98") (name "/SPI_DI") (class "Default")
      (node (ref "U1") (pin "65") (pinfunction "IO_L3P_D0_DIN_MISO_MISO1_2_65") (pintype "bidirectional"))
    )
    (net (code "99") (name "/SPI_DO") (class "Default")
      (node (ref "U1") (pin "64") (pinfunction "IO_L3N_MOSI_CSI_B_MISO0_2_64") (pintype "bidirectional"))
    )
    (net (code "100") (name "/TCK") (class "Default")
      (node (ref "J1") (pin "2") (pinfunction "2_2") (pintype "passive"))
      (node (ref "R24") (pin "2") (pinfunction "2_2") (pintype "passive"))
      (node (ref "U1") (pin "109") (pinfunction "TCK_109") (pintype "input"))
    )
    (net (code "101") (name "/TDI") (class "Default")
      (node (ref "J1") (pin "3") (pinfunction "3_3") (pintype "passive"))
      (node (ref "R22") (pin "2") (pinfunction "2_2") (pintype "passive"))
      (node (ref "U1") (pin "110") (pinfunction "TDI_110") (pintype "input"))
    )
    (net (code "102") (name "/TDO") (class "Default")
      (node (ref "J1") (pin "4") (pinfunction "4_4") (pintype "passive"))
      (node (ref "R25") (pin "2") (pinfunction "2_2") (pintype "passive"))
      (node (ref "U1") (pin "106") (pinfunction "TDO_106") (pintype "output"))
    )
    (net (code "103") (name "/TMS") (class "Default")
      (node (ref "J1") (pin "5") (pinfunction "5_5") (pintype "passive"))
      (node (ref "R23") (pin "2") (pinfunction "2_2") (pintype "passive"))
      (node (ref "U1") (pin "107") (pinfunction "TMS_107") (pintype "input"))
    )
    (net (code "111") (name "/~{CAS}") (class "Default")
      (node (ref "U1") (pin "45") (pinfunction "IO_L49N_D4_2_45") (pintype "bidirectional"))
    )
    (net (code "112") (name "/~{CS}") (class "Default")
      (node (ref "R8") (pin "2") (pinfunction "2_2") (pintype "passive"))
      (node (ref "U1") (pin "39") (pinfunction "IO_L65P_INIT_B_2_39") (pintype "bidirectional"))
    )
    (net (code "113") (name "/~{OE}") (class "Default")
      (node (ref "U1") (pin "114") (pinfunction "IO_L65N_SCP2_0_114") (pintype "bidirectional+no_connect"))
    )
    (net (code "114") (name "/~{RAS}") (class "Default")
      (node (ref "U1") (pin "44") (pinfunction "IO_L62P_D5_2_44") (pintype "bidirectional"))
    )
    (net (code "115") (name "/~{RD}") (class "Default")
      (node (ref "U1") (pin "124") (pinfunction "IO_L37P_GCLK13_0_124") (pintype "bidirectional+no_connect"))
    )
    (net (code "116") (name "/~{RXF}") (class "Default")
      (node (ref "U1") (pin "117") (pinfunction "IO_L64P_SCP5_0_117") (pintype "bidirectional+no_connect"))
    )
    (net (code "117") (name "/~{TXE}") (class "Default")
      (node (ref "U1") (pin "126") (pinfunction "IO_L36N_GCLK14_0_126") (pintype "bidirectional+no_connect"))
    )
    (net (code "118") (name "/~{WE}") (class "Default")
      (node (ref "U1") (pin "46") (pinfunction "IO_L49P_D3_2_46") (pintype "bidirectional"))
    )
    (net (code "119") (name "/~{WR}") (class "Default")
      (node (ref "U1") (pin "121") (pinfunction "IO_L62P_0_121") (pintype "bidirectional+no_connect"))
    )
    (net (code "120") (name "GND") (class "Default")
      (node (ref "C10") (pin "1") (pinfunction "1_1") (pintype "passive"))
      (node (ref "C11") (pin "1") (pinfunction "1_1") (pintype "passive"))
      (node (ref "C12") (pin "1") (pinfunction "1_1") (pintype "passive"))
      (node (ref "C13") (pin "1") (pinfunction "1_1") (pintype "passive"))
      (node (ref "C14") (pin "1") (pinfunction "1_1") (pintype "passive"))
      (node (ref "C15") (pin "1") (pinfunction "1_1") (pintype "passive"))
      (node (ref "C16") (pin "1") (pinfunction "1_1") (pintype "passive"))
      (node (ref "C17") (pin "1") (pinfunction "1_1") (pintype "passive"))
      (node (ref "C18") (pin "1") (pinfunction "1_1") (pintype "passive"))
      (node (ref "C19") (pin "1") (pinfunction "1_1") (pintype "passive"))
      (node (ref "C20") (pin "1") (pinfunction "1_1") (pintype "passive"))
      (node (ref "C21") (pin "1") (pinfunction "1_1") (pintype "passive"))
      (node (ref "C22") (pin "1") (pinfunction "1_1") (pintype "passive"))
      (node (ref "C23") (pin "1") (pinfunction "1_1") (pintype "passive"))
      (node (ref "C24") (pin "1") (pinfunction "1_1") (pintype "passive"))
      (node (ref "C25") (pin "1") (pinfunction "1_1") (pintype "passive"))
      (node (ref "C26") (pin "1") (pinfunction "1_1") (pintype "passive"))
      (node (ref "C27") (pin "1") (pinfunction "1_1") (pintype "passive"))
      (node (ref "C3") (pin "1") (pinfunction "1_1") (pintype "passive"))
      (node (ref "C4") (pin "1") (pinfunction "1_1") (pintype "passive"))
      (node (ref "C5") (pin "1") (pinfunction "1_1") (pintype "passive"))
      (node (ref "C6") (pin "1") (pinfunction "1_1") (pintype "passive"))
      (node (ref "C7") (pin "1") (pinfunction "1_1") (pintype "passive"))
      (node (ref "C74") (pin "1") (pinfunction "1_1") (pintype "passive"))
      (node (ref "C75") (pin "1") (pinfunction "1_1") (pintype "passive"))
      (node (ref "C8") (pin "1") (pinfunction "1_1") (pintype "passive"))
      (node (ref "C9") (pin "1") (pinfunction "1_1") (pintype "passive"))
      (node (ref "J1") (pin "6") (pinfunction "6_6") (pintype "passive"))
      (node (ref "LED3") (pin "2") (pinfunction "2_2") (pintype "passive"))
      (node (ref "S3") (pin "3") (pinfunction "B_3") (pintype "passive"))
      (node (ref "S3") (pin "4") (pinfunction "B'_4") (pintype "passive"))
      (node (ref "S3") (pin "5") (pinfunction "GND_5") (pintype "passive"))
      (node (ref "S3") (pin "6") (pinfunction "GND_6") (pintype "passive"))
      (node (ref "S4") (pin "3") (pinfunction "B_3") (pintype "passive"))
      (node (ref "S4") (pin "4") (pinfunction "B'_4") (pintype "passive"))
      (node (ref "S4") (pin "5") (pinfunction "GND_5") (pintype "passive"))
      (node (ref "S4") (pin "6") (pinfunction "GND_6") (pintype "passive"))
      (node (ref "U1") (pin "108") (pinfunction "GND_108") (pintype "power_in"))
      (node (ref "U1") (pin "113") (pinfunction "GND_113") (pintype "power_in"))
      (node (ref "U1") (pin "13") (pinfunction "GND_13") (pintype "power_in"))
      (node (ref "U1") (pin "130") (pinfunction "GND_130") (pintype "power_in"))
      (node (ref "U1") (pin "136") (pinfunction "GND_136") (pintype "power_in"))
      (node (ref "U1") (pin "144") (pinfunction "IO_L1P_HSWAPEN_0_144") (pintype "bidirectional"))
      (node (ref "U1") (pin "25") (pinfunction "GND_25") (pintype "power_in"))
      (node (ref "U1") (pin "3") (pinfunction "GND_3") (pintype "power_in"))
      (node (ref "U1") (pin "49") (pinfunction "GND_49") (pintype "power_in"))
      (node (ref "U1") (pin "54") (pinfunction "GND_54") (pintype "power_in"))
      (node (ref "U1") (pin "68") (pinfunction "GND_68") (pintype "power_in"))
      (node (ref "U1") (pin "73") (pinfunction "SUSPEND_73") (pintype "input"))
      (node (ref "U1") (pin "77") (pinfunction "GND_77") (pintype "power_in"))
      (node (ref "U1") (pin "91") (pinfunction "GND_91") (pintype "power_in"))
      (node (ref "U1") (pin "96") (pinfunction "GND_96") (pintype "power_in"))
      (node (ref "U2") (pin "2") (pinfunction "GND_2") (pintype "passive"))
    )
    (net (code "121") (name "V1P2") (class "Default")
      (node (ref "C15") (pin "2") (pinfunction "2_2") (pintype "passive"))
      (node (ref "C16") (pin "2") (pinfunction "2_2") (pintype "passive"))
      (node (ref "C17") (pin "2") (pinfunction "2_2") (pintype "passive"))
      (node (ref "C18") (pin "2") (pinfunction "2_2") (pintype "passive"))
      (node (ref "U1") (pin "128") (pinfunction "VCCINT_128") (pintype "power_in"))
      (node (ref "U1") (pin "19") (pinfunction "VCCINT_19") (pintype "power_in"))
      (node (ref "U1") (pin "28") (pinfunction "VCCINT_28") (pintype "power_in"))
      (node (ref "U1") (pin "52") (pinfunction "VCCINT_52") (pintype "power_in"))
      (node (ref "U1") (pin "89") (pinfunction "VCCINT_89") (pintype "power_in"))
    )
    (net (code "122") (name "V3P3") (class "Default")
      (node (ref "C10") (pin "2") (pinfunction "2_2") (pintype "passive"))
      (node (ref "C11") (pin "2") (pinfunction "2_2") (pintype "passive"))
      (node (ref "C12") (pin "2") (pinfunction "2_2") (pintype "passive"))
      (node (ref "C13") (pin "2") (pinfunction "2_2") (pintype "passive"))
      (node (ref "C14") (pin "2") (pinfunction "2_2") (pintype "passive"))
      (node (ref "C19") (pin "2") (pinfunction "2_2") (pintype "passive"))
      (node (ref "C20") (pin "2") (pinfunction "2_2") (pintype "passive"))
      (node (ref "C21") (pin "2") (pinfunction "2_2") (pintype "passive"))
      (node (ref "C22") (pin "2") (pinfunction "2_2") (pintype "passive"))
      (node (ref "C23") (pin "2") (pinfunction "2_2") (pintype "passive"))
      (node (ref "C24") (pin "2") (pinfunction "2_2") (pintype "passive"))
      (node (ref "C25") (pin "2") (pinfunction "2_2") (pintype "passive"))
      (node (ref "C26") (pin "2") (pinfunction "2_2") (pintype "passive"))
      (node (ref "C27") (pin "2") (pinfunction "2_2") (pintype "passive"))
      (node (ref "C3") (pin "2") (pinfunction "2_2") (pintype "passive"))
      (node (ref "C4") (pin "2") (pinfunction "2_2") (pintype "passive"))
      (node (ref "C5") (pin "2") (pinfunction "2_2") (pintype "passive"))
      (node (ref "C6") (pin "2") (pinfunction "2_2") (pintype "passive"))
      (node (ref "C7") (pin "2") (pinfunction "2_2") (pintype "passive"))
      (node (ref "C8") (pin "2") (pinfunction "2_2") (pintype "passive"))
      (node (ref "C9") (pin "2") (pinfunction "2_2") (pintype "passive"))
      (node (ref "J1") (pin "1") (pinfunction "1_1") (pintype "passive"))
      (node (ref "R22") (pin "1") (pinfunction "1_1") (pintype "passive"))
      (node (ref "R23") (pin "1") (pinfunction "1_1") (pintype "passive"))
      (node (ref "R24") (pin "1") (pinfunction "1_1") (pintype "passive"))
      (node (ref "R25") (pin "1") (pinfunction "1_1") (pintype "passive"))
      (node (ref "R26") (pin "1") (pinfunction "1_1") (pintype "passive"))
      (node (ref "R7") (pin "1") (pinfunction "1_1") (pintype "passive"))
      (node (ref "R8") (pin "1") (pinfunction "1_1") (pintype "passive"))
      (node (ref "R9") (pin "1") (pinfunction "1_1") (pintype "passive"))
      (node (ref "U1") (pin "103") (pinfunction "VCCO_1_103") (pintype "power_in"))
      (node (ref "U1") (pin "122") (pinfunction "VCCO_0_122") (pintype "power_in"))
      (node (ref "U1") (pin "125") (pinfunction "VCCO_0_125") (pintype "power_in"))
      (node (ref "U1") (pin "129") (pinfunction "VCCAUX_129") (pintype "power_in"))
      (node (ref "U1") (pin "135") (pinfunction "VCCO_0_135") (pintype "power_in"))
      (node (ref "U1") (pin "18") (pinfunction "VCCO_3_18") (pintype "power_in"))
      (node (ref "U1") (pin "20") (pinfunction "VCCAUX_20") (pintype "power_in"))
      (node (ref "U1") (pin "31") (pinfunction "VCCO_3_31") (pintype "power_in"))
      (node (ref "U1") (pin "36") (pinfunction "VCCAUX_36") (pintype "power_in"))
      (node (ref "U1") (pin "4") (pinfunction "VCCO_3_4") (pintype "power_in"))
      (node (ref "U1") (pin "42") (pinfunction "VCCO_2_42") (pintype "power_in"))
      (node (ref "U1") (pin "53") (pinfunction "VCCAUX_53") (pintype "power_in"))
      (node (ref "U1") (pin "63") (pinfunction "VCCO_2_63") (pintype "power_in"))
      (node (ref "U1") (pin "69") (pinfunction "IO_L1N_M0_CMPMISO_2_69") (pintype "bidirectional"))
      (node (ref "U1") (pin "76") (pinfunction "VCCO_1_76") (pintype "power_in"))
      (node (ref "U1") (pin "86") (pinfunction "VCCO_1_86") (pintype "power_in"))
      (node (ref "U1") (pin "90") (pinfunction "VCCAUX_90") (pintype "power_in"))
      (node (ref "U2") (pin "1") (pinfunction "EOH_1") (pintype "passive"))
      (node (ref "U2") (pin "4") (pinfunction "VCC_4") (pintype "passive"))
    )
    (net (code "123") (name "unconnected-(S3-A'-Pad2)") (class "Default")
      (node (ref "S3") (pin "2") (pinfunction "A'_2") (pintype "passive+no_connect"))
    )
    (net (code "124") (name "unconnected-(S4-A'-Pad2)") (class "Default")
      (node (ref "S4") (pin "2") (pinfunction "A'_2") (pintype "passive+no_connect"))
    )
    (net (code "125") (name "unconnected-(U1A-IO_L66P_SCP1_0-Pad112)") (class "Default")
      (node (ref "U1") (pin "112") (pinfunction "IO_L66P_SCP1_0_112") (pintype "bidirectional+no_connect"))
    )
    (net (code "126") (name "unconnected-(U1E-CMPCS_B_2-Pad72)") (class "Default")
      (node (ref "U1") (pin "72") (pinfunction "CMPCS_B_2_72") (pintype "input+no_connect"))
    )
  )
)
